# neonred-live-2026-10-06.net
KiCad netlist of a schematic drawn in EasyEDA
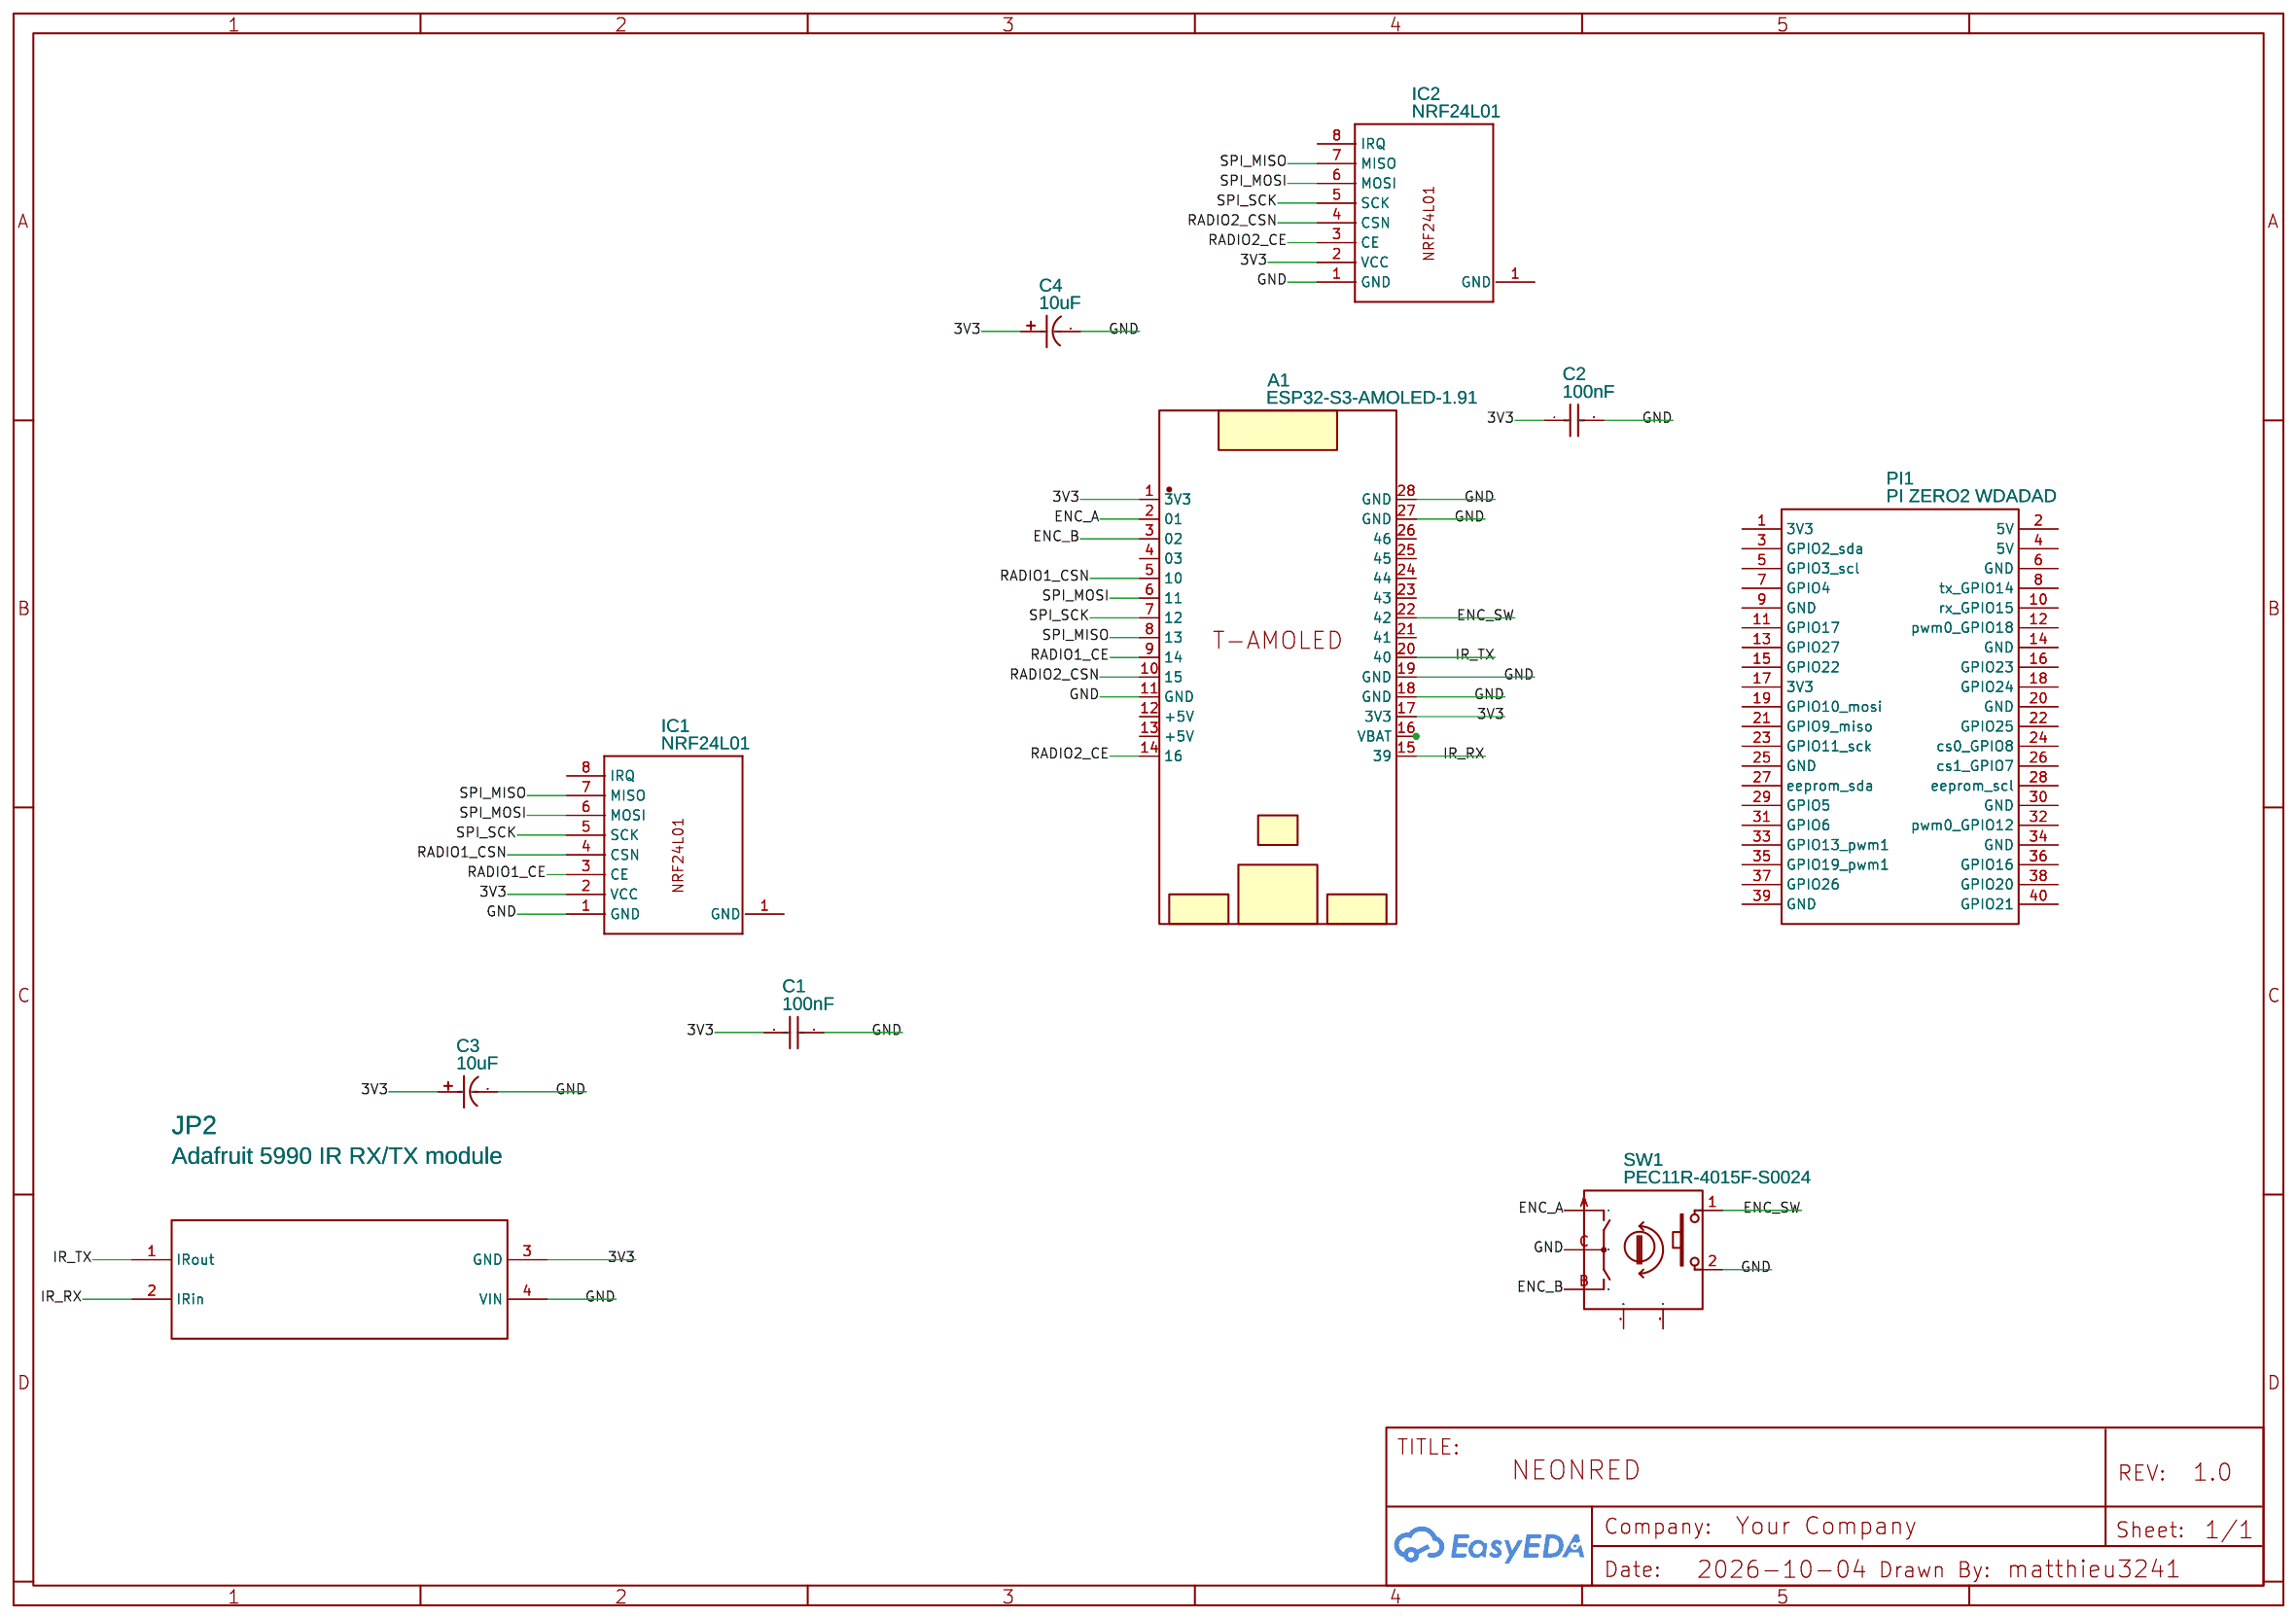
[diagram p0: schematic sheet]

(export (version "E")
  (design (tool "Eeschema 10.0.6"))
  (components
    (comp (ref "A1")
      (value "ESP32-S3-AMOLED-1.91")
      (fields (field (name "Manufacturer Part") "T-Display S3 AMOLED") (field (name "Manufacturer") "Lilygo"))
      (libsource (lib "") (part "ESP32-S3-AMOLED-1.91"))
    )
    (comp (ref "C1")
      (value "100nF")
      (fields (field (name "Manufacturer Part") "0.1UF(104) +-20% 63v"))
      (libsource (lib "") (part "100nF"))
    )
    (comp (ref "C2")
      (value "100nF")
      (fields (field (name "Manufacturer Part") "0.1UF(104) +-20% 63v"))
      (libsource (lib "") (part "100nF"))
    )
    (comp (ref "C3") (value "10uF") (libsource (lib "") (part "Capacitor 10uF TH")))
    (comp (ref "C4") (value "10uF") (libsource (lib "") (part "Capacitor 10uF TH")))
    (comp (ref "IC1") (value "NRF24L01") (libsource (lib "") (part "NRF24L01")))
    (comp (ref "IC2") (value "NRF24L01") (libsource (lib "") (part "NRF24L01")))
    (comp (ref "JP2") (value "Adafruit 5990 IR RX/TX module") (libsource (lib "") (part "M04")))
    (comp (ref "PI1") (value "PI ZERO2 WDADAD") (libsource (lib "") (part "PI ZERO2 WDADAD")))
    (comp (ref "SW1")
      (value "PEC11R-4015F-S0024")
      (fields (field (name "Manufacturer") "BOURNS"))
      (libsource (lib "") (part "PEC11R-4015F-S0024"))
    )
  )
  (nets
    (net (code "1") (name "/3V3") (class "Default")
      (node (ref "A1") (pin "1") (pinfunction "3V3_1") (pintype "unspecified"))
      (node (ref "A1") (pin "17") (pinfunction "3V3_17") (pintype "unspecified"))
      (node (ref "C1") (pin "1") (pinfunction "1_1") (pintype "input"))
      (node (ref "C2") (pin "1") (pinfunction "1_1") (pintype "input"))
      (node (ref "C3") (pin "1") (pinfunction "1_1") (pintype "input"))
      (node (ref "C4") (pin "1") (pinfunction "1_1") (pintype "input"))
      (node (ref "IC1") (pin "2") (pinfunction "VCC_2") (pintype "bidirectional"))
      (node (ref "IC2") (pin "2") (pinfunction "VCC_2") (pintype "bidirectional"))
      (node (ref "JP2") (pin "3") (pinfunction "GND_3") (pintype "unspecified"))
    )
    (net (code "2") (name "/ENC_A") (class "Default")
      (node (ref "A1") (pin "2") (pinfunction "01_2") (pintype "unspecified"))
      (node (ref "SW1") (pin "A") (pinfunction "A_A") (pintype "unspecified"))
    )
    (net (code "3") (name "/ENC_B") (class "Default")
      (node (ref "A1") (pin "3") (pinfunction "02_3") (pintype "unspecified"))
      (node (ref "SW1") (pin "B") (pinfunction "B_B") (pintype "unspecified"))
    )
    (net (code "4") (name "/ENC_SW") (class "Default")
      (node (ref "A1") (pin "22") (pinfunction "42_22") (pintype "unspecified"))
      (node (ref "SW1") (pin "1") (pinfunction "1_1") (pintype "unspecified"))
    )
    (net (code "5") (name "/GND") (class "Default")
      (node (ref "A1") (pin "11") (pinfunction "GND_11") (pintype "unspecified"))
      (node (ref "A1") (pin "18") (pinfunction "GND_18") (pintype "unspecified"))
      (node (ref "A1") (pin "19") (pinfunction "GND_19") (pintype "unspecified"))
      (node (ref "A1") (pin "27") (pinfunction "GND_27") (pintype "unspecified"))
      (node (ref "A1") (pin "28") (pinfunction "GND_28") (pintype "unspecified"))
      (node (ref "C1") (pin "2") (pinfunction "2_2") (pintype "input"))
      (node (ref "C2") (pin "2") (pinfunction "2_2") (pintype "input"))
      (node (ref "C3") (pin "2") (pinfunction "2_2") (pintype "input"))
      (node (ref "C4") (pin "2") (pinfunction "2_2") (pintype "input"))
      (node (ref "IC1") (pin "1") (pinfunction "GND_1") (pintype "bidirectional"))
      (node (ref "IC2") (pin "1") (pinfunction "GND_1") (pintype "bidirectional"))
      (node (ref "JP2") (pin "4") (pinfunction "VIN_4") (pintype "unspecified"))
      (node (ref "SW1") (pin "2") (pinfunction "2_2") (pintype "unspecified"))
      (node (ref "SW1") (pin "C") (pinfunction "C_C") (pintype "unspecified"))
    )
    (net (code "6") (name "/IR_RX") (class "Default")
      (node (ref "A1") (pin "15") (pinfunction "39_15") (pintype "unspecified"))
      (node (ref "JP2") (pin "2") (pinfunction "IRin_2") (pintype "unspecified"))
    )
    (net (code "7") (name "/IR_TX") (class "Default")
      (node (ref "A1") (pin "20") (pinfunction "40_20") (pintype "unspecified"))
      (node (ref "JP2") (pin "1") (pinfunction "IRout_1") (pintype "unspecified"))
    )
    (net (code "8") (name "/RADIO1_CE") (class "Default")
      (node (ref "A1") (pin "9") (pinfunction "14_9") (pintype "unspecified"))
      (node (ref "IC1") (pin "3") (pinfunction "CE_3") (pintype "bidirectional"))
    )
    (net (code "9") (name "/RADIO1_CSN") (class "Default")
      (node (ref "A1") (pin "5") (pinfunction "10_5") (pintype "unspecified"))
      (node (ref "IC1") (pin "4") (pinfunction "CSN_4") (pintype "bidirectional"))
    )
    (net (code "10") (name "/RADIO2_CE") (class "Default")
      (node (ref "A1") (pin "14") (pinfunction "16_14") (pintype "unspecified"))
      (node (ref "IC2") (pin "3") (pinfunction "CE_3") (pintype "bidirectional"))
    )
    (net (code "11") (name "/RADIO2_CSN") (class "Default")
      (node (ref "A1") (pin "10") (pinfunction "15_10") (pintype "unspecified"))
      (node (ref "IC2") (pin "4") (pinfunction "CSN_4") (pintype "bidirectional"))
    )
    (net (code "12") (name "/SPI_MISO") (class "Default")
      (node (ref "A1") (pin "8") (pinfunction "13_8") (pintype "unspecified"))
      (node (ref "IC1") (pin "7") (pinfunction "MISO_7") (pintype "bidirectional"))
      (node (ref "IC2") (pin "7") (pinfunction "MISO_7") (pintype "bidirectional"))
    )
    (net (code "13") (name "/SPI_MOSI") (class "Default")
      (node (ref "A1") (pin "6") (pinfunction "11_6") (pintype "unspecified"))
      (node (ref "IC1") (pin "6") (pinfunction "MOSI_6") (pintype "bidirectional"))
      (node (ref "IC2") (pin "6") (pinfunction "MOSI_6") (pintype "bidirectional"))
    )
    (net (code "14") (name "/SPI_SCK") (class "Default")
      (node (ref "A1") (pin "7") (pinfunction "12_7") (pintype "unspecified"))
      (node (ref "IC1") (pin "5") (pinfunction "SCK_5") (pintype "bidirectional"))
      (node (ref "IC2") (pin "5") (pinfunction "SCK_5") (pintype "bidirectional"))
    )
    (net (code "15") (name "unconnected-(A1-+5V-Pad12)") (class "Default")
      (node (ref "A1") (pin "12") (pinfunction "+5V_12") (pintype "unspecified"))
    )
    (net (code "16") (name "unconnected-(A1-+5V-Pad13)") (class "Default")
      (node (ref "A1") (pin "13") (pinfunction "+5V_13") (pintype "unspecified"))
    )
    (net (code "17") (name "unconnected-(A1-03-Pad4)") (class "Default")
      (node (ref "A1") (pin "4") (pinfunction "03_4") (pintype "unspecified"))
    )
    (net (code "18") (name "unconnected-(A1-41-Pad21)") (class "Default")
      (node (ref "A1") (pin "21") (pinfunction "41_21") (pintype "unspecified"))
    )
    (net (code "19") (name "unconnected-(A1-43-Pad23)") (class "Default")
      (node (ref "A1") (pin "23") (pinfunction "43_23") (pintype "unspecified"))
    )
    (net (code "20") (name "unconnected-(A1-44-Pad24)") (class "Default")
      (node (ref "A1") (pin "24") (pinfunction "44_24") (pintype "unspecified"))
    )
    (net (code "21") (name "unconnected-(A1-45-Pad25)") (class "Default")
      (node (ref "A1") (pin "25") (pinfunction "45_25") (pintype "unspecified"))
    )
    (net (code "22") (name "unconnected-(A1-46-Pad26)") (class "Default")
      (node (ref "A1") (pin "26") (pinfunction "46_26") (pintype "unspecified"))
    )
    (net (code "23") (name "unconnected-(A1-VBAT-Pad16)") (class "Default")
      (node (ref "A1") (pin "16") (pinfunction "VBAT_16") (pintype "unspecified"))
    )
    (net (code "24") (name "unconnected-(IC1-GND-Pad1)") (class "Default")
      (node (ref "IC1") (pin "1") (pinfunction "GND_1") (pintype "bidirectional"))
    )
    (net (code "25") (name "unconnected-(IC1-IRQ-Pad8)") (class "Default")
      (node (ref "IC1") (pin "8") (pinfunction "IRQ_8") (pintype "bidirectional"))
    )
    (net (code "26") (name "unconnected-(IC2-GND-Pad1)") (class "Default")
      (node (ref "IC2") (pin "1") (pinfunction "GND_1") (pintype "bidirectional"))
    )
    (net (code "27") (name "unconnected-(IC2-IRQ-Pad8)") (class "Default")
      (node (ref "IC2") (pin "8") (pinfunction "IRQ_8") (pintype "bidirectional"))
    )
    (net (code "28") (name "unconnected-(PI1-3V3-Pad1)") (class "Default")
      (node (ref "PI1") (pin "1") (pinfunction "3V3_1") (pintype "unspecified"))
    )
    (net (code "29") (name "unconnected-(PI1-3V3-Pad17)") (class "Default")
      (node (ref "PI1") (pin "17") (pinfunction "3V3_17") (pintype "unspecified"))
    )
    (net (code "30") (name "unconnected-(PI1-5V-Pad2)") (class "Default")
      (node (ref "PI1") (pin "2") (pinfunction "5V_2") (pintype "unspecified"))
    )
    (net (code "31") (name "unconnected-(PI1-5V-Pad4)") (class "Default")
      (node (ref "PI1") (pin "4") (pinfunction "5V_4") (pintype "unspecified"))
    )
    (net (code "32") (name "unconnected-(PI1-GND-Pad6)") (class "Default")
      (node (ref "PI1") (pin "6") (pinfunction "GND_6") (pintype "unspecified"))
    )
    (net (code "33") (name "unconnected-(PI1-GND-Pad9)") (class "Default")
      (node (ref "PI1") (pin "9") (pinfunction "GND_9") (pintype "unspecified"))
    )
    (net (code "34") (name "unconnected-(PI1-GND-Pad14)") (class "Default")
      (node (ref "PI1") (pin "14") (pinfunction "GND_14") (pintype "unspecified"))
    )
    (net (code "35") (name "unconnected-(PI1-GND-Pad20)") (class "Default")
      (node (ref "PI1") (pin "20") (pinfunction "GND_20") (pintype "unspecified"))
    )
    (net (code "36") (name "unconnected-(PI1-GND-Pad25)") (class "Default")
      (node (ref "PI1") (pin "25") (pinfunction "GND_25") (pintype "unspecified"))
    )
    (net (code "37") (name "unconnected-(PI1-GND-Pad30)") (class "Default")
      (node (ref "PI1") (pin "30") (pinfunction "GND_30") (pintype "unspecified"))
    )
    (net (code "38") (name "unconnected-(PI1-GND-Pad34)") (class "Default")
      (node (ref "PI1") (pin "34") (pinfunction "GND_34") (pintype "unspecified"))
    )
    (net (code "39") (name "unconnected-(PI1-GND-Pad39)") (class "Default")
      (node (ref "PI1") (pin "39") (pinfunction "GND_39") (pintype "unspecified"))
    )
    (net (code "40") (name "unconnected-(PI1-GPIO2_sda-Pad3)") (class "Default")
      (node (ref "PI1") (pin "3") (pinfunction "GPIO2_sda_3") (pintype "unspecified"))
    )
    (net (code "41") (name "unconnected-(PI1-GPIO3_scl-Pad5)") (class "Default")
      (node (ref "PI1") (pin "5") (pinfunction "GPIO3_scl_5") (pintype "unspecified"))
    )
    (net (code "42") (name "unconnected-(PI1-GPIO4-Pad7)") (class "Default")
      (node (ref "PI1") (pin "7") (pinfunction "GPIO4_7") (pintype "unspecified"))
    )
    (net (code "43") (name "unconnected-(PI1-GPIO5-Pad29)") (class "Default")
      (node (ref "PI1") (pin "29") (pinfunction "GPIO5_29") (pintype "unspecified"))
    )
    (net (code "44") (name "unconnected-(PI1-GPIO6-Pad31)") (class "Default")
      (node (ref "PI1") (pin "31") (pinfunction "GPIO6_31") (pintype "unspecified"))
    )
    (net (code "45") (name "unconnected-(PI1-GPIO9_miso-Pad21)") (class "Default")
      (node (ref "PI1") (pin "21") (pinfunction "GPIO9_miso_21") (pintype "unspecified"))
    )
    (net (code "46") (name "unconnected-(PI1-GPIO10_mosi-Pad19)") (class "Default")
      (node (ref "PI1") (pin "19") (pinfunction "GPIO10_mosi_19") (pintype "unspecified"))
    )
    (net (code "47") (name "unconnected-(PI1-GPIO11_sck-Pad23)") (class "Default")
      (node (ref "PI1") (pin "23") (pinfunction "GPIO11_sck_23") (pintype "unspecified"))
    )
    (net (code "48") (name "unconnected-(PI1-GPIO13_pwm1-Pad33)") (class "Default")
      (node (ref "PI1") (pin "33") (pinfunction "GPIO13_pwm1_33") (pintype "unspecified"))
    )
    (net (code "49") (name "unconnected-(PI1-GPIO16-Pad36)") (class "Default")
      (node (ref "PI1") (pin "36") (pinfunction "GPIO16_36") (pintype "unspecified"))
    )
    (net (code "50") (name "unconnected-(PI1-GPIO17-Pad11)") (class "Default")
      (node (ref "PI1") (pin "11") (pinfunction "GPIO17_11") (pintype "unspecified"))
    )
    (net (code "51") (name "unconnected-(PI1-GPIO19_pwm1-Pad35)") (class "Default")
      (node (ref "PI1") (pin "35") (pinfunction "GPIO19_pwm1_35") (pintype "unspecified"))
    )
    (net (code "52") (name "unconnected-(PI1-GPIO20-Pad38)") (class "Default")
      (node (ref "PI1") (pin "38") (pinfunction "GPIO20_38") (pintype "unspecified"))
    )
    (net (code "53") (name "unconnected-(PI1-GPIO21-Pad40)") (class "Default")
      (node (ref "PI1") (pin "40") (pinfunction "GPIO21_40") (pintype "unspecified"))
    )
    (net (code "54") (name "unconnected-(PI1-GPIO22-Pad15)") (class "Default")
      (node (ref "PI1") (pin "15") (pinfunction "GPIO22_15") (pintype "unspecified"))
    )
    (net (code "55") (name "unconnected-(PI1-GPIO23-Pad16)") (class "Default")
      (node (ref "PI1") (pin "16") (pinfunction "GPIO23_16") (pintype "unspecified"))
    )
    (net (code "56") (name "unconnected-(PI1-GPIO24-Pad18)") (class "Default")
      (node (ref "PI1") (pin "18") (pinfunction "GPIO24_18") (pintype "unspecified"))
    )
    (net (code "57") (name "unconnected-(PI1-GPIO25-Pad22)") (class "Default")
      (node (ref "PI1") (pin "22") (pinfunction "GPIO25_22") (pintype "unspecified"))
    )
    (net (code "58") (name "unconnected-(PI1-GPIO26-Pad37)") (class "Default")
      (node (ref "PI1") (pin "37") (pinfunction "GPIO26_37") (pintype "unspecified"))
    )
    (net (code "59") (name "unconnected-(PI1-GPIO27-Pad13)") (class "Default")
      (node (ref "PI1") (pin "13") (pinfunction "GPIO27_13") (pintype "unspecified"))
    )
    (net (code "60") (name "unconnected-(PI1-cs0_GPIO8-Pad24)") (class "Default")
      (node (ref "PI1") (pin "24") (pinfunction "cs0_GPIO8_24") (pintype "unspecified"))
    )
    (net (code "61") (name "unconnected-(PI1-cs1_GPIO7-Pad26)") (class "Default")
      (node (ref "PI1") (pin "26") (pinfunction "cs1_GPIO7_26") (pintype "unspecified"))
    )
    (net (code "62") (name "unconnected-(PI1-eeprom_scl-Pad28)") (class "Default")
      (node (ref "PI1") (pin "28") (pinfunction "eeprom_scl_28") (pintype "unspecified"))
    )
    (net (code "63") (name "unconnected-(PI1-eeprom_sda-Pad27)") (class "Default")
      (node (ref "PI1") (pin "27") (pinfunction "eeprom_sda_27") (pintype "unspecified"))
    )
    (net (code "64") (name "unconnected-(PI1-pwm0_GPIO12-Pad32)") (class "Default")
      (node (ref "PI1") (pin "32") (pinfunction "pwm0_GPIO12_32") (pintype "unspecified"))
    )
    (net (code "65") (name "unconnected-(PI1-pwm0_GPIO18-Pad12)") (class "Default")
      (node (ref "PI1") (pin "12") (pinfunction "pwm0_GPIO18_12") (pintype "unspecified"))
    )
    (net (code "66") (name "unconnected-(PI1-rx_GPIO15-Pad10)") (class "Default")
      (node (ref "PI1") (pin "10") (pinfunction "rx_GPIO15_10") (pintype "unspecified"))
    )
    (net (code "67") (name "unconnected-(PI1-tx_GPIO14-Pad8)") (class "Default")
      (node (ref "PI1") (pin "8") (pinfunction "tx_GPIO14_8") (pintype "unspecified"))
    )
    (net (code "68") (name "unconnected-(SW1-PadMT1)") (class "Default")
      (node (ref "SW1") (pin "MT1") (pinfunction "MT1_MT1") (pintype "unspecified"))
    )
    (net (code "69") (name "unconnected-(SW1-PadMT2)") (class "Default")
      (node (ref "SW1") (pin "MT2") (pinfunction "MT2_MT2") (pintype "unspecified"))
    )
  )
)
